# brmeeg.net
KiCad netlist of a schematic drawn in EAGLE
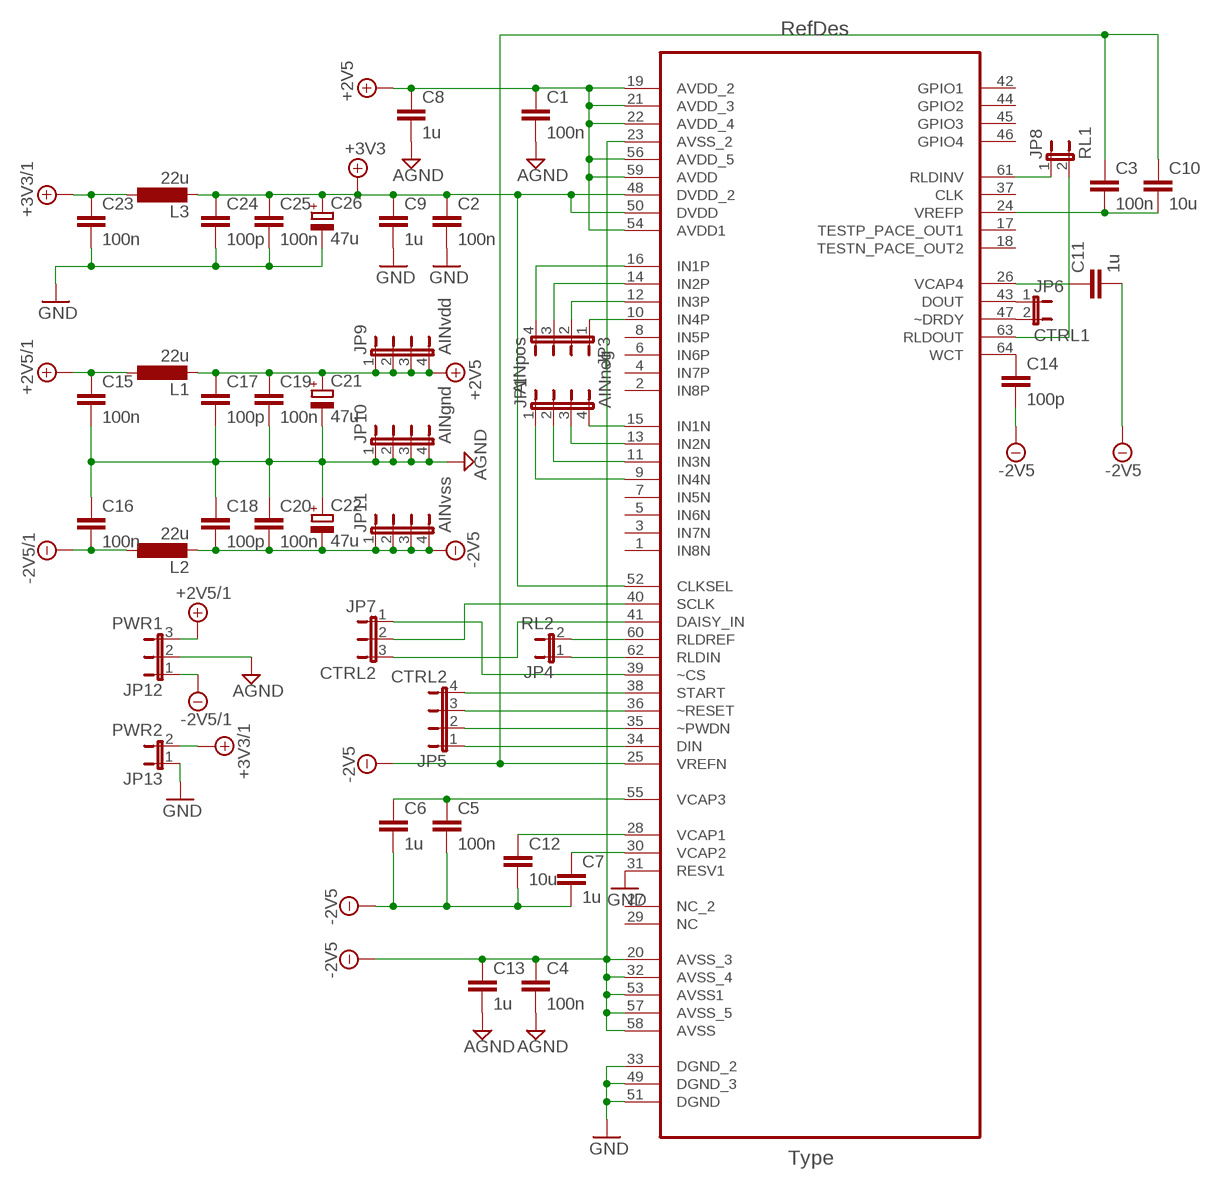
[diagram p0: schematic, sheet 1]

(export (version "E")
  (design (tool "Eeschema 10.0.6"))
  (components
    (comp (ref "C1")
      (value "100n")
      (footprint "eagle-import:C0603K")
      (libsource (lib "eagle-import") (part "C-EUC0603K"))
    )
    (comp (ref "C2")
      (value "100n")
      (footprint "eagle-import:C0603K")
      (libsource (lib "eagle-import") (part "C-EUC0603K"))
    )
    (comp (ref "C3")
      (value "100n")
      (footprint "eagle-import:C0603K")
      (libsource (lib "eagle-import") (part "C-EUC0603K"))
    )
    (comp (ref "C4")
      (value "100n")
      (footprint "eagle-import:C0603K")
      (libsource (lib "eagle-import") (part "C-EUC0603K"))
    )
    (comp (ref "C5")
      (value "100n")
      (footprint "eagle-import:C0603K")
      (libsource (lib "eagle-import") (part "C-EUC0603K"))
    )
    (comp (ref "C6")
      (value "1u")
      (footprint "eagle-import:C0805K")
      (libsource (lib "eagle-import") (part "C-EUC0805K"))
    )
    (comp (ref "C7")
      (value "1u")
      (footprint "eagle-import:C0805K")
      (libsource (lib "eagle-import") (part "C-EUC0805K"))
    )
    (comp (ref "C8")
      (value "1u")
      (footprint "eagle-import:C0805K")
      (libsource (lib "eagle-import") (part "C-EUC0805K"))
    )
    (comp (ref "C9")
      (value "1u")
      (footprint "eagle-import:C0805K")
      (libsource (lib "eagle-import") (part "C-EUC0805K"))
    )
    (comp (ref "C10")
      (value "10u")
      (footprint "eagle-import:C0805K")
      (libsource (lib "eagle-import") (part "C-EUC0805K"))
    )
    (comp (ref "C11")
      (value "1u")
      (footprint "eagle-import:C0805K")
      (libsource (lib "eagle-import") (part "C-EUC0805K"))
    )
    (comp (ref "C12")
      (value "10u")
      (footprint "eagle-import:C0805K")
      (libsource (lib "eagle-import") (part "C-EUC0805K"))
    )
    (comp (ref "C13")
      (value "1u")
      (footprint "eagle-import:C0805K")
      (libsource (lib "eagle-import") (part "C-EUC0805K"))
    )
    (comp (ref "C14")
      (value "100p")
      (footprint "eagle-import:C0603K")
      (libsource (lib "eagle-import") (part "C-EUC0603K"))
    )
    (comp (ref "C15")
      (value "100n")
      (footprint "eagle-import:C0603K")
      (libsource (lib "eagle-import") (part "C-EUC0603K"))
    )
    (comp (ref "C16")
      (value "100n")
      (footprint "eagle-import:C0603K")
      (libsource (lib "eagle-import") (part "C-EUC0603K"))
    )
    (comp (ref "C17")
      (value "100p")
      (footprint "eagle-import:C0603K")
      (libsource (lib "eagle-import") (part "C-EUC0603K"))
    )
    (comp (ref "C18")
      (value "100p")
      (footprint "eagle-import:C0603K")
      (libsource (lib "eagle-import") (part "C-EUC0603K"))
    )
    (comp (ref "C19")
      (value "100n")
      (footprint "eagle-import:C0603K")
      (libsource (lib "eagle-import") (part "C-EUC0603K"))
    )
    (comp (ref "C20")
      (value "100n")
      (footprint "eagle-import:C0603K")
      (libsource (lib "eagle-import") (part "C-EUC0603K"))
    )
    (comp (ref "C21")
      (value "47u")
      (footprint "eagle-import:SMC_C")
      (libsource (lib "eagle-import") (part "CPOL-EUSMCC"))
    )
    (comp (ref "C22")
      (value "47u")
      (footprint "eagle-import:SMC_C")
      (libsource (lib "eagle-import") (part "CPOL-EUSMCC"))
    )
    (comp (ref "C23")
      (value "100n")
      (footprint "eagle-import:C0603K")
      (libsource (lib "eagle-import") (part "C-EUC0603K"))
    )
    (comp (ref "C24")
      (value "100p")
      (footprint "eagle-import:C0603K")
      (libsource (lib "eagle-import") (part "C-EUC0603K"))
    )
    (comp (ref "C25")
      (value "100n")
      (footprint "eagle-import:C0603K")
      (libsource (lib "eagle-import") (part "C-EUC0603K"))
    )
    (comp (ref "C26")
      (value "47u")
      (footprint "eagle-import:SMC_C")
      (libsource (lib "eagle-import") (part "CPOL-EUSMCC"))
    )
    (comp (ref "JP1")
      (value "AINneg")
      (footprint "eagle-import:JP4")
      (libsource (lib "eagle-import") (part "JP4E"))
    )
    (comp (ref "JP3")
      (value "AINpos")
      (footprint "eagle-import:JP4")
      (libsource (lib "eagle-import") (part "JP4E"))
    )
    (comp (ref "JP4")
      (value "RL2")
      (footprint "eagle-import:JP1")
      (libsource (lib "eagle-import") (part "JP1E"))
    )
    (comp (ref "JP5")
      (value "CTRL2")
      (footprint "eagle-import:JP4")
      (libsource (lib "eagle-import") (part "JP4E"))
    )
    (comp (ref "JP6")
      (value "CTRL1")
      (footprint "eagle-import:JP1")
      (libsource (lib "eagle-import") (part "JP1E"))
    )
    (comp (ref "JP7")
      (value "CTRL2")
      (footprint "eagle-import:JP2")
      (libsource (lib "eagle-import") (part "JP2E"))
    )
    (comp (ref "JP8")
      (value "RL1")
      (footprint "eagle-import:JP1")
      (libsource (lib "eagle-import") (part "JP1E"))
    )
    (comp (ref "JP9")
      (value "AINvdd")
      (footprint "eagle-import:JP4")
      (libsource (lib "eagle-import") (part "JP4E"))
    )
    (comp (ref "JP10")
      (value "AINgnd")
      (footprint "eagle-import:JP4")
      (libsource (lib "eagle-import") (part "JP4E"))
    )
    (comp (ref "JP11")
      (value "AINvss")
      (footprint "eagle-import:JP4")
      (libsource (lib "eagle-import") (part "JP4E"))
    )
    (comp (ref "JP12")
      (value "PWR1")
      (footprint "eagle-import:JP2")
      (libsource (lib "eagle-import") (part "JP2E"))
    )
    (comp (ref "JP13")
      (value "PWR2")
      (footprint "eagle-import:JP1")
      (libsource (lib "eagle-import") (part "JP1E"))
    )
    (comp (ref "L1")
      (value "22u")
      (footprint "eagle-import:L1812")
      (libsource (lib "eagle-import") (part "L-EUL1812"))
    )
    (comp (ref "L2")
      (value "22u")
      (footprint "eagle-import:L1812")
      (libsource (lib "eagle-import") (part "L-EUL1812"))
    )
    (comp (ref "L3")
      (value "22u")
      (footprint "eagle-import:L1812")
      (libsource (lib "eagle-import") (part "L-EUL1812"))
    )
    (comp (ref "U1")
      (value "ADS1194CPAG")
      (footprint "eagle-import:QFP50P1200X1200X120-64N")
      (libsource (lib "eagle-import") (part "ADS1194CPAG"))
    )
  )
  (nets
    (net (code "1") (name "+2V5") (class "Default")
      (node (ref "C1") (pin "1") (pinfunction "1_1") (pintype "passive"))
      (node (ref "C17") (pin "1") (pinfunction "1_1") (pintype "passive"))
      (node (ref "C19") (pin "1") (pinfunction "1_1") (pintype "passive"))
      (node (ref "C21") (pin "+") (pinfunction "+_+") (pintype "passive"))
      (node (ref "C8") (pin "1") (pinfunction "1_1") (pintype "passive"))
      (node (ref "JP9") (pin "1") (pinfunction "1_1") (pintype "passive"))
      (node (ref "JP9") (pin "2") (pinfunction "2_2") (pintype "passive"))
      (node (ref "JP9") (pin "3") (pinfunction "3_3") (pintype "passive"))
      (node (ref "JP9") (pin "4") (pinfunction "4_4") (pintype "passive"))
      (node (ref "L1") (pin "2") (pinfunction "2_2") (pintype "passive"))
      (node (ref "U1") (pin "19") (pinfunction "AVDD_2_19") (pintype "power_in"))
      (node (ref "U1") (pin "21") (pinfunction "AVDD_3_21") (pintype "power_in"))
      (node (ref "U1") (pin "22") (pinfunction "AVDD_4_22") (pintype "power_in"))
      (node (ref "U1") (pin "54") (pinfunction "AVDD1_54") (pintype "power_in"))
      (node (ref "U1") (pin "56") (pinfunction "AVDD_5_56") (pintype "power_in"))
      (node (ref "U1") (pin "59") (pinfunction "AVDD_59") (pintype "power_in"))
    )
    (net (code "2") (name "+2V5{slash}1") (class "Default")
      (node (ref "C15") (pin "1") (pinfunction "1_1") (pintype "passive"))
      (node (ref "JP12") (pin "3") (pinfunction "3_3") (pintype "passive"))
      (node (ref "L1") (pin "1") (pinfunction "1_1") (pintype "passive"))
    )
    (net (code "3") (name "+3V3") (class "Default")
      (node (ref "C2") (pin "1") (pinfunction "1_1") (pintype "passive"))
      (node (ref "C24") (pin "1") (pinfunction "1_1") (pintype "passive"))
      (node (ref "C25") (pin "1") (pinfunction "1_1") (pintype "passive"))
      (node (ref "C26") (pin "+") (pinfunction "+_+") (pintype "passive"))
      (node (ref "C9") (pin "1") (pinfunction "1_1") (pintype "passive"))
      (node (ref "L3") (pin "2") (pinfunction "2_2") (pintype "passive"))
      (node (ref "U1") (pin "48") (pinfunction "DVDD_2_48") (pintype "power_in"))
      (node (ref "U1") (pin "50") (pinfunction "DVDD_50") (pintype "power_in"))
      (node (ref "U1") (pin "52") (pinfunction "CLKSEL_52") (pintype "input"))
    )
    (net (code "4") (name "+3V3{slash}1") (class "Default")
      (node (ref "C23") (pin "1") (pinfunction "1_1") (pintype "passive"))
      (node (ref "JP13") (pin "2") (pinfunction "2_2") (pintype "passive"))
      (node (ref "L3") (pin "1") (pinfunction "1_1") (pintype "passive"))
    )
    (net (code "5") (name "-2V5") (class "Default")
      (node (ref "C10") (pin "1") (pinfunction "1_1") (pintype "passive"))
      (node (ref "C11") (pin "2") (pinfunction "2_2") (pintype "passive"))
      (node (ref "C12") (pin "2") (pinfunction "2_2") (pintype "passive"))
      (node (ref "C13") (pin "1") (pinfunction "1_1") (pintype "passive"))
      (node (ref "C14") (pin "2") (pinfunction "2_2") (pintype "passive"))
      (node (ref "C18") (pin "2") (pinfunction "2_2") (pintype "passive"))
      (node (ref "C20") (pin "2") (pinfunction "2_2") (pintype "passive"))
      (node (ref "C22") (pin "-") (pinfunction "-_-") (pintype "passive"))
      (node (ref "C3") (pin "1") (pinfunction "1_1") (pintype "passive"))
      (node (ref "C4") (pin "1") (pinfunction "1_1") (pintype "passive"))
      (node (ref "C5") (pin "2") (pinfunction "2_2") (pintype "passive"))
      (node (ref "C6") (pin "2") (pinfunction "2_2") (pintype "passive"))
      (node (ref "C7") (pin "2") (pinfunction "2_2") (pintype "passive"))
      (node (ref "JP11") (pin "1") (pinfunction "1_1") (pintype "passive"))
      (node (ref "JP11") (pin "2") (pinfunction "2_2") (pintype "passive"))
      (node (ref "JP11") (pin "3") (pinfunction "3_3") (pintype "passive"))
      (node (ref "JP11") (pin "4") (pinfunction "4_4") (pintype "passive"))
      (node (ref "L2") (pin "2") (pinfunction "2_2") (pintype "passive"))
      (node (ref "U1") (pin "20") (pinfunction "AVSS_3_20") (pintype "power_in"))
      (node (ref "U1") (pin "23") (pinfunction "AVSS_2_23") (pintype "power_in"))
      (node (ref "U1") (pin "25") (pinfunction "VREFN_25") (pintype "input"))
      (node (ref "U1") (pin "32") (pinfunction "AVSS_4_32") (pintype "power_in"))
      (node (ref "U1") (pin "53") (pinfunction "AVSS1_53") (pintype "power_in"))
      (node (ref "U1") (pin "57") (pinfunction "AVSS_5_57") (pintype "power_in"))
      (node (ref "U1") (pin "58") (pinfunction "AVSS_58") (pintype "power_in"))
    )
    (net (code "6") (name "-2V5{slash}1") (class "Default")
      (node (ref "C16") (pin "2") (pinfunction "2_2") (pintype "passive"))
      (node (ref "JP12") (pin "1") (pinfunction "1_1") (pintype "passive"))
      (node (ref "L2") (pin "1") (pinfunction "1_1") (pintype "passive"))
    )
    (net (code "7") (name "AGND") (class "Default")
      (node (ref "C1") (pin "2") (pinfunction "2_2") (pintype "passive"))
      (node (ref "C13") (pin "2") (pinfunction "2_2") (pintype "passive"))
      (node (ref "C15") (pin "2") (pinfunction "2_2") (pintype "passive"))
      (node (ref "C16") (pin "1") (pinfunction "1_1") (pintype "passive"))
      (node (ref "C17") (pin "2") (pinfunction "2_2") (pintype "passive"))
      (node (ref "C18") (pin "1") (pinfunction "1_1") (pintype "passive"))
      (node (ref "C19") (pin "2") (pinfunction "2_2") (pintype "passive"))
      (node (ref "C20") (pin "1") (pinfunction "1_1") (pintype "passive"))
      (node (ref "C21") (pin "-") (pinfunction "-_-") (pintype "passive"))
      (node (ref "C22") (pin "+") (pinfunction "+_+") (pintype "passive"))
      (node (ref "C4") (pin "2") (pinfunction "2_2") (pintype "passive"))
      (node (ref "C8") (pin "2") (pinfunction "2_2") (pintype "passive"))
      (node (ref "JP10") (pin "1") (pinfunction "1_1") (pintype "passive"))
      (node (ref "JP10") (pin "2") (pinfunction "2_2") (pintype "passive"))
      (node (ref "JP10") (pin "3") (pinfunction "3_3") (pintype "passive"))
      (node (ref "JP10") (pin "4") (pinfunction "4_4") (pintype "passive"))
      (node (ref "JP12") (pin "2") (pinfunction "2_2") (pintype "passive"))
    )
    (net (code "8") (name "GND") (class "Default")
      (node (ref "C2") (pin "2") (pinfunction "2_2") (pintype "passive"))
      (node (ref "C23") (pin "2") (pinfunction "2_2") (pintype "passive"))
      (node (ref "C24") (pin "2") (pinfunction "2_2") (pintype "passive"))
      (node (ref "C25") (pin "2") (pinfunction "2_2") (pintype "passive"))
      (node (ref "C26") (pin "-") (pinfunction "-_-") (pintype "passive"))
      (node (ref "C9") (pin "2") (pinfunction "2_2") (pintype "passive"))
      (node (ref "JP13") (pin "1") (pinfunction "1_1") (pintype "passive"))
      (node (ref "U1") (pin "31") (pinfunction "RESV1_31") (pintype "passive"))
      (node (ref "U1") (pin "33") (pinfunction "DGND_2_33") (pintype "passive"))
      (node (ref "U1") (pin "49") (pinfunction "DGND_3_49") (pintype "passive"))
      (node (ref "U1") (pin "51") (pinfunction "DGND_51") (pintype "passive"))
    )
    (net (code "9") (name "Net-(U1-DAISY_IN)") (class "Default")
      (node (ref "JP7") (pin "3") (pinfunction "3_3") (pintype "passive"))
      (node (ref "U1") (pin "41") (pinfunction "DAISY_IN_41") (pintype "input"))
    )
    (net (code "10") (name "Net-(U1-DIN)") (class "Default")
      (node (ref "JP5") (pin "1") (pinfunction "1_1") (pintype "passive"))
      (node (ref "U1") (pin "34") (pinfunction "DIN_34") (pintype "input"))
    )
    (net (code "11") (name "Net-(U1-DOUT)") (class "Default")
      (node (ref "JP6") (pin "1") (pinfunction "1_1") (pintype "passive"))
      (node (ref "U1") (pin "43") (pinfunction "DOUT_43") (pintype "output"))
    )
    (net (code "12") (name "Net-(U1-IN1N)") (class "Default")
      (node (ref "JP1") (pin "4") (pinfunction "4_4") (pintype "passive"))
      (node (ref "U1") (pin "15") (pinfunction "IN1N_15") (pintype "input"))
    )
    (net (code "13") (name "Net-(U1-IN1P)") (class "Default")
      (node (ref "JP3") (pin "4") (pinfunction "4_4") (pintype "passive"))
      (node (ref "U1") (pin "16") (pinfunction "IN1P_16") (pintype "input"))
    )
    (net (code "14") (name "Net-(U1-IN2N)") (class "Default")
      (node (ref "JP1") (pin "3") (pinfunction "3_3") (pintype "passive"))
      (node (ref "U1") (pin "13") (pinfunction "IN2N_13") (pintype "input"))
    )
    (net (code "15") (name "Net-(U1-IN2P)") (class "Default")
      (node (ref "JP3") (pin "3") (pinfunction "3_3") (pintype "passive"))
      (node (ref "U1") (pin "14") (pinfunction "IN2P_14") (pintype "input"))
    )
    (net (code "16") (name "Net-(U1-IN3N)") (class "Default")
      (node (ref "JP1") (pin "2") (pinfunction "2_2") (pintype "passive"))
      (node (ref "U1") (pin "11") (pinfunction "IN3N_11") (pintype "input"))
    )
    (net (code "17") (name "Net-(U1-IN3P)") (class "Default")
      (node (ref "JP3") (pin "2") (pinfunction "2_2") (pintype "passive"))
      (node (ref "U1") (pin "12") (pinfunction "IN3P_12") (pintype "input"))
    )
    (net (code "18") (name "Net-(U1-IN4N)") (class "Default")
      (node (ref "JP1") (pin "1") (pinfunction "1_1") (pintype "passive"))
      (node (ref "U1") (pin "9") (pinfunction "IN4N_9") (pintype "input"))
    )
    (net (code "19") (name "Net-(U1-IN4P)") (class "Default")
      (node (ref "JP3") (pin "1") (pinfunction "1_1") (pintype "passive"))
      (node (ref "U1") (pin "10") (pinfunction "IN4P_10") (pintype "input"))
    )
    (net (code "20") (name "Net-(U1-RLDIN)") (class "Default")
      (node (ref "JP4") (pin "1") (pinfunction "1_1") (pintype "passive"))
      (node (ref "U1") (pin "62") (pinfunction "RLDIN_62") (pintype "input"))
    )
    (net (code "21") (name "Net-(U1-RLDINV)") (class "Default")
      (node (ref "JP8") (pin "1") (pinfunction "1_1") (pintype "passive"))
      (node (ref "U1") (pin "61") (pinfunction "RLDINV_61") (pintype "bidirectional"))
    )
    (net (code "22") (name "Net-(U1-RLDOUT)") (class "Default")
      (node (ref "JP8") (pin "2") (pinfunction "2_2") (pintype "passive"))
      (node (ref "U1") (pin "63") (pinfunction "RLDOUT_63") (pintype "output"))
    )
    (net (code "23") (name "Net-(U1-RLDREF)") (class "Default")
      (node (ref "JP4") (pin "2") (pinfunction "2_2") (pintype "passive"))
      (node (ref "U1") (pin "60") (pinfunction "RLDREF_60") (pintype "input"))
    )
    (net (code "24") (name "Net-(U1-SCLK)") (class "Default")
      (node (ref "JP7") (pin "2") (pinfunction "2_2") (pintype "passive"))
      (node (ref "U1") (pin "40") (pinfunction "SCLK_40") (pintype "input"))
    )
    (net (code "25") (name "Net-(U1-START)") (class "Default")
      (node (ref "JP5") (pin "4") (pinfunction "4_4") (pintype "passive"))
      (node (ref "U1") (pin "38") (pinfunction "START_38") (pintype "input"))
    )
    (net (code "26") (name "Net-(U1-VCAP1)") (class "Default")
      (node (ref "C12") (pin "1") (pinfunction "1_1") (pintype "passive"))
      (node (ref "U1") (pin "28") (pinfunction "VCAP1_28") (pintype "passive"))
    )
    (net (code "27") (name "Net-(U1-VCAP2)") (class "Default")
      (node (ref "C7") (pin "1") (pinfunction "1_1") (pintype "passive"))
      (node (ref "U1") (pin "30") (pinfunction "VCAP2_30") (pintype "passive"))
    )
    (net (code "28") (name "Net-(U1-VCAP3)") (class "Default")
      (node (ref "C5") (pin "1") (pinfunction "1_1") (pintype "passive"))
      (node (ref "C6") (pin "1") (pinfunction "1_1") (pintype "passive"))
      (node (ref "U1") (pin "55") (pinfunction "VCAP3_55") (pintype "passive"))
    )
    (net (code "29") (name "Net-(U1-VCAP4)") (class "Default")
      (node (ref "C11") (pin "1") (pinfunction "1_1") (pintype "passive"))
      (node (ref "U1") (pin "26") (pinfunction "VCAP4_26") (pintype "output"))
    )
    (net (code "30") (name "Net-(U1-VREFP)") (class "Default")
      (node (ref "C10") (pin "2") (pinfunction "2_2") (pintype "passive"))
      (node (ref "C3") (pin "2") (pinfunction "2_2") (pintype "passive"))
      (node (ref "U1") (pin "24") (pinfunction "VREFP_24") (pintype "bidirectional"))
    )
    (net (code "31") (name "Net-(U1-WCT)") (class "Default")
      (node (ref "C14") (pin "1") (pinfunction "1_1") (pintype "passive"))
      (node (ref "U1") (pin "64") (pinfunction "WCT_64") (pintype "output"))
    )
    (net (code "32") (name "Net-(U1-~{CS})") (class "Default")
      (node (ref "JP7") (pin "1") (pinfunction "1_1") (pintype "passive"))
      (node (ref "U1") (pin "39") (pinfunction "~{CS}_39") (pintype "input"))
    )
    (net (code "33") (name "Net-(U1-~{DRDY})") (class "Default")
      (node (ref "JP6") (pin "2") (pinfunction "2_2") (pintype "passive"))
      (node (ref "U1") (pin "47") (pinfunction "~{DRDY}_47") (pintype "output"))
    )
    (net (code "34") (name "Net-(U1-~{PWDN})") (class "Default")
      (node (ref "JP5") (pin "2") (pinfunction "2_2") (pintype "passive"))
      (node (ref "U1") (pin "35") (pinfunction "~{PWDN}_35") (pintype "input"))
    )
    (net (code "35") (name "Net-(U1-~{RESET})") (class "Default")
      (node (ref "JP5") (pin "3") (pinfunction "3_3") (pintype "passive"))
      (node (ref "U1") (pin "36") (pinfunction "~{RESET}_36") (pintype "input"))
    )
    (net (code "36") (name "unconnected-(U1-CLK-Pad37)") (class "Default")
      (node (ref "U1") (pin "37") (pinfunction "CLK_37") (pintype "bidirectional"))
    )
    (net (code "37") (name "unconnected-(U1-GPIO1-Pad42)") (class "Default")
      (node (ref "U1") (pin "42") (pinfunction "GPIO1_42") (pintype "bidirectional"))
    )
    (net (code "38") (name "unconnected-(U1-GPIO2-Pad44)") (class "Default")
      (node (ref "U1") (pin "44") (pinfunction "GPIO2_44") (pintype "bidirectional"))
    )
    (net (code "39") (name "unconnected-(U1-GPIO3-Pad45)") (class "Default")
      (node (ref "U1") (pin "45") (pinfunction "GPIO3_45") (pintype "bidirectional"))
    )
    (net (code "40") (name "unconnected-(U1-GPIO4-Pad46)") (class "Default")
      (node (ref "U1") (pin "46") (pinfunction "GPIO4_46") (pintype "bidirectional"))
    )
    (net (code "41") (name "unconnected-(U1-IN5N-Pad7)") (class "Default")
      (node (ref "U1") (pin "7") (pinfunction "IN5N_7") (pintype "input"))
    )
    (net (code "42") (name "unconnected-(U1-IN5P-Pad8)") (class "Default")
      (node (ref "U1") (pin "8") (pinfunction "IN5P_8") (pintype "input"))
    )
    (net (code "43") (name "unconnected-(U1-IN6N-Pad5)") (class "Default")
      (node (ref "U1") (pin "5") (pinfunction "IN6N_5") (pintype "input"))
    )
    (net (code "44") (name "unconnected-(U1-IN6P-Pad6)") (class "Default")
      (node (ref "U1") (pin "6") (pinfunction "IN6P_6") (pintype "input"))
    )
    (net (code "45") (name "unconnected-(U1-IN7N-Pad3)") (class "Default")
      (node (ref "U1") (pin "3") (pinfunction "IN7N_3") (pintype "input"))
    )
    (net (code "46") (name "unconnected-(U1-IN7P-Pad4)") (class "Default")
      (node (ref "U1") (pin "4") (pinfunction "IN7P_4") (pintype "input"))
    )
    (net (code "47") (name "unconnected-(U1-IN8N-Pad1)") (class "Default")
      (node (ref "U1") (pin "1") (pinfunction "IN8N_1") (pintype "input"))
    )
    (net (code "48") (name "unconnected-(U1-IN8P-Pad2)") (class "Default")
      (node (ref "U1") (pin "2") (pinfunction "IN8P_2") (pintype "input"))
    )
    (net (code "49") (name "unconnected-(U1-NC-Pad29)") (class "Default")
      (node (ref "U1") (pin "29") (pinfunction "NC_29") (pintype "no_connect"))
    )
    (net (code "50") (name "unconnected-(U1-NC_2-Pad27)") (class "Default")
      (node (ref "U1") (pin "27") (pinfunction "NC_2_27") (pintype "no_connect"))
    )
    (net (code "51") (name "unconnected-(U1-TESTN_PACE_OUT2-Pad18)") (class "Default")
      (node (ref "U1") (pin "18") (pinfunction "TESTN_PACE_OUT2_18") (pintype "bidirectional"))
    )
    (net (code "52") (name "unconnected-(U1-TESTP_PACE_OUT1-Pad17)") (class "Default")
      (node (ref "U1") (pin "17") (pinfunction "TESTP_PACE_OUT1_17") (pintype "bidirectional"))
    )
  )
)
